# PHOTODIODE.net
KiCad netlist of a schematic drawn in Altium Designer
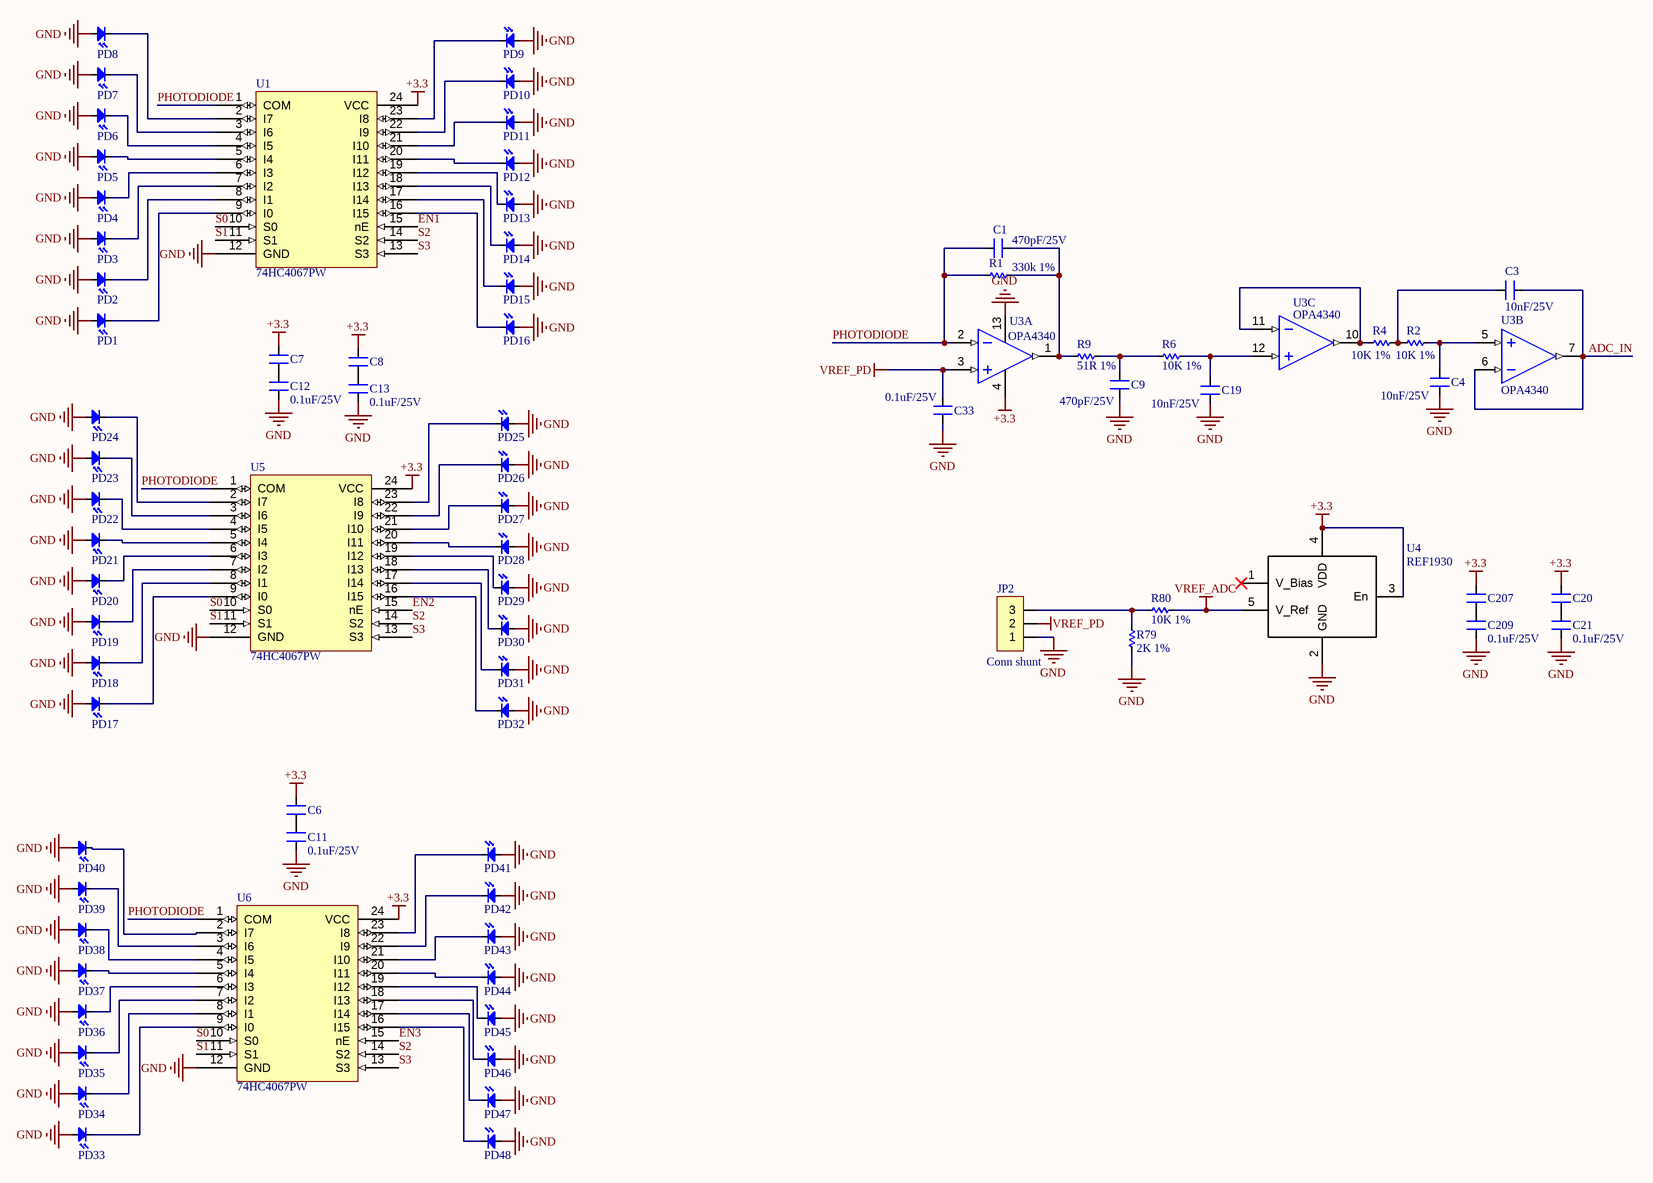
[diagram p0: PHOTODIODE.SchDoc]

(export (version "E")
  (design (tool "Eeschema 10.0.6"))
  (components
    (comp (ref "C1")
      (value "470pF/25V")
      (footprint "SM-0603")
      (description "0603")
      (libsource (lib "Capacitors") (part "CM"))
    )
    (comp (ref "C3")
      (value "10nF/25V")
      (footprint "SM-0603")
      (description "0603")
      (libsource (lib "Capacitors") (part "CM"))
    )
    (comp (ref "C4")
      (value "10nF/25V")
      (footprint "SM-0603")
      (description "0603")
      (libsource (lib "Capacitors") (part "CM"))
    )
    (comp (ref "C6")
      (value "0.1uF/25V")
      (footprint "SM-0603")
      (description "0603")
      (libsource (lib "Capacitors") (part "CM"))
    )
    (comp (ref "C7")
      (value "0.1uF/25V")
      (footprint "SM-0603")
      (description "0603")
      (libsource (lib "Capacitors") (part "CM"))
    )
    (comp (ref "C8")
      (value "0.1uF/25V")
      (footprint "SM-0603")
      (description "0603")
      (libsource (lib "Capacitors") (part "CM"))
    )
    (comp (ref "C9")
      (value "470pF/25V")
      (footprint "SM-0603")
      (description "0603")
      (libsource (lib "Capacitors") (part "CM"))
    )
    (comp (ref "C11")
      (value "0.1uF/25V")
      (footprint "SM-0603")
      (description "0603")
      (libsource (lib "Capacitors") (part "CM"))
    )
    (comp (ref "C12")
      (value "0.1uF/25V")
      (footprint "SM-0603")
      (description "0603")
      (libsource (lib "Capacitors") (part "CM"))
    )
    (comp (ref "C13")
      (value "0.1uF/25V")
      (footprint "SM-0603")
      (description "0603")
      (libsource (lib "Capacitors") (part "CM"))
    )
    (comp (ref "C19")
      (value "10nF/25V")
      (footprint "SM-0603")
      (description "0603")
      (libsource (lib "Capacitors") (part "CM"))
    )
    (comp (ref "C20")
      (value "0.1uF/25V")
      (footprint "SM-0603")
      (description "0603")
      (libsource (lib "Capacitors") (part "CM"))
    )
    (comp (ref "C21")
      (value "0.1uF/25V")
      (footprint "SM-0603")
      (description "0603")
      (libsource (lib "Capacitors") (part "CM"))
    )
    (comp (ref "C33")
      (value "0.1uF/25V")
      (footprint "SM-0603")
      (description "0603")
      (libsource (lib "Capacitors") (part "CM"))
    )
    (comp (ref "C207")
      (value "0.1uF/25V")
      (footprint "SM-0603")
      (description "0603")
      (libsource (lib "Capacitors") (part "CM"))
    )
    (comp (ref "C209")
      (value "0.1uF/25V")
      (footprint "SM-0603")
      (description "0603")
      (libsource (lib "Capacitors") (part "CM"))
    )
    (comp (ref "JP2")
      (value "Conn shunt")
      (footprint "M50-3930342")
      (description "WR-PHD 2.54 mm Angled Socket Header")
      (fields
        (field (name "MANUFACTURER") "Würth Elektronik eiSos GmbH")
        (field (name "PARTNO") "613003143121")
        (field (name "CREATED BY") "Karrer Zheng")
      )
      (libsource (lib "Library") (part "JP3"))
    )
    (comp (ref "PD1")
      (value "Photodiode")
      (footprint "VEMD5080X01")
      (libsource (lib "Library") (part "Photodiode"))
    )
    (comp (ref "PD2")
      (value "Photodiode")
      (footprint "VEMD5080X01")
      (libsource (lib "Library") (part "Photodiode"))
    )
    (comp (ref "PD3")
      (value "Photodiode")
      (footprint "VEMD5080X01")
      (libsource (lib "Library") (part "Photodiode"))
    )
    (comp (ref "PD4")
      (value "Photodiode")
      (footprint "VEMD5080X01")
      (libsource (lib "Library") (part "Photodiode"))
    )
    (comp (ref "PD5")
      (value "Photodiode")
      (footprint "VEMD5080X01")
      (libsource (lib "Library") (part "Photodiode"))
    )
    (comp (ref "PD6")
      (value "Photodiode")
      (footprint "VEMD5080X01")
      (libsource (lib "Library") (part "Photodiode"))
    )
    (comp (ref "PD7")
      (value "Photodiode")
      (footprint "VEMD5080X01")
      (libsource (lib "Library") (part "Photodiode"))
    )
    (comp (ref "PD8")
      (value "Photodiode")
      (footprint "VEMD5080X01")
      (libsource (lib "Library") (part "Photodiode"))
    )
    (comp (ref "PD9")
      (value "Photodiode")
      (footprint "VEMD5080X01")
      (libsource (lib "Library") (part "Photodiode"))
    )
    (comp (ref "PD10")
      (value "Photodiode")
      (footprint "VEMD5080X01")
      (libsource (lib "Library") (part "Photodiode"))
    )
    (comp (ref "PD11")
      (value "Photodiode")
      (footprint "VEMD5080X01")
      (libsource (lib "Library") (part "Photodiode"))
    )
    (comp (ref "PD12")
      (value "Photodiode")
      (footprint "VEMD5080X01")
      (libsource (lib "Library") (part "Photodiode"))
    )
    (comp (ref "PD13")
      (value "Photodiode")
      (footprint "VEMD5080X01")
      (libsource (lib "Library") (part "Photodiode"))
    )
    (comp (ref "PD14")
      (value "Photodiode")
      (footprint "VEMD5080X01")
      (libsource (lib "Library") (part "Photodiode"))
    )
    (comp (ref "PD15")
      (value "Photodiode")
      (footprint "VEMD5080X01")
      (libsource (lib "Library") (part "Photodiode"))
    )
    (comp (ref "PD16")
      (value "Photodiode")
      (footprint "VEMD5080X01")
      (libsource (lib "Library") (part "Photodiode"))
    )
    (comp (ref "PD17")
      (value "Photodiode")
      (footprint "VEMD5080X01")
      (libsource (lib "Library") (part "Photodiode"))
    )
    (comp (ref "PD18")
      (value "Photodiode")
      (footprint "VEMD5080X01")
      (libsource (lib "Library") (part "Photodiode"))
    )
    (comp (ref "PD19")
      (value "Photodiode")
      (footprint "VEMD5080X01")
      (libsource (lib "Library") (part "Photodiode"))
    )
    (comp (ref "PD20")
      (value "Photodiode")
      (footprint "VEMD5080X01")
      (libsource (lib "Library") (part "Photodiode"))
    )
    (comp (ref "PD21")
      (value "Photodiode")
      (footprint "VEMD5080X01")
      (libsource (lib "Library") (part "Photodiode"))
    )
    (comp (ref "PD22")
      (value "Photodiode")
      (footprint "VEMD5080X01")
      (libsource (lib "Library") (part "Photodiode"))
    )
    (comp (ref "PD23")
      (value "Photodiode")
      (footprint "VEMD5080X01")
      (libsource (lib "Library") (part "Photodiode"))
    )
    (comp (ref "PD24")
      (value "Photodiode")
      (footprint "VEMD5080X01")
      (libsource (lib "Library") (part "Photodiode"))
    )
    (comp (ref "PD25")
      (value "Photodiode")
      (footprint "VEMD5080X01")
      (libsource (lib "Library") (part "Photodiode"))
    )
    (comp (ref "PD26")
      (value "Photodiode")
      (footprint "VEMD5080X01")
      (libsource (lib "Library") (part "Photodiode"))
    )
    (comp (ref "PD27")
      (value "Photodiode")
      (footprint "VEMD5080X01")
      (libsource (lib "Library") (part "Photodiode"))
    )
    (comp (ref "PD28")
      (value "Photodiode")
      (footprint "VEMD5080X01")
      (libsource (lib "Library") (part "Photodiode"))
    )
    (comp (ref "PD29")
      (value "Photodiode")
      (footprint "VEMD5080X01")
      (libsource (lib "Library") (part "Photodiode"))
    )
    (comp (ref "PD30")
      (value "Photodiode")
      (footprint "VEMD5080X01")
      (libsource (lib "Library") (part "Photodiode"))
    )
    (comp (ref "PD31")
      (value "Photodiode")
      (footprint "VEMD5080X01")
      (libsource (lib "Library") (part "Photodiode"))
    )
    (comp (ref "PD32")
      (value "Photodiode")
      (footprint "VEMD5080X01")
      (libsource (lib "Library") (part "Photodiode"))
    )
    (comp (ref "PD33")
      (value "Photodiode")
      (footprint "VEMD5080X01")
      (libsource (lib "Library") (part "Photodiode"))
    )
    (comp (ref "PD34")
      (value "Photodiode")
      (footprint "VEMD5080X01")
      (libsource (lib "Library") (part "Photodiode"))
    )
    (comp (ref "PD35")
      (value "Photodiode")
      (footprint "VEMD5080X01")
      (libsource (lib "Library") (part "Photodiode"))
    )
    (comp (ref "PD36")
      (value "Photodiode")
      (footprint "VEMD5080X01")
      (libsource (lib "Library") (part "Photodiode"))
    )
    (comp (ref "PD37")
      (value "Photodiode")
      (footprint "VEMD5080X01")
      (libsource (lib "Library") (part "Photodiode"))
    )
    (comp (ref "PD38")
      (value "Photodiode")
      (footprint "VEMD5080X01")
      (libsource (lib "Library") (part "Photodiode"))
    )
    (comp (ref "PD39")
      (value "Photodiode")
      (footprint "VEMD5080X01")
      (libsource (lib "Library") (part "Photodiode"))
    )
    (comp (ref "PD40")
      (value "Photodiode")
      (footprint "VEMD5080X01")
      (libsource (lib "Library") (part "Photodiode"))
    )
    (comp (ref "PD41")
      (value "Photodiode")
      (footprint "VEMD5080X01")
      (libsource (lib "Library") (part "Photodiode"))
    )
    (comp (ref "PD42")
      (value "Photodiode")
      (footprint "VEMD5080X01")
      (libsource (lib "Library") (part "Photodiode"))
    )
    (comp (ref "PD43")
      (value "Photodiode")
      (footprint "VEMD5080X01")
      (libsource (lib "Library") (part "Photodiode"))
    )
    (comp (ref "PD44")
      (value "Photodiode")
      (footprint "VEMD5080X01")
      (libsource (lib "Library") (part "Photodiode"))
    )
    (comp (ref "PD45")
      (value "Photodiode")
      (footprint "VEMD5080X01")
      (libsource (lib "Library") (part "Photodiode"))
    )
    (comp (ref "PD46")
      (value "Photodiode")
      (footprint "VEMD5080X01")
      (libsource (lib "Library") (part "Photodiode"))
    )
    (comp (ref "PD47")
      (value "Photodiode")
      (footprint "VEMD5080X01")
      (libsource (lib "Library") (part "Photodiode"))
    )
    (comp (ref "PD48")
      (value "Photodiode")
      (footprint "VEMD5080X01")
      (libsource (lib "Library") (part "Photodiode"))
    )
    (comp (ref "R1")
      (value "330k 1%")
      (footprint "RES-SMD-0603")
      (description "0603")
      (fields
        (field (name "MANUFACTURER") "Generic Components")
        (field (name "PUBLISHER") "Altium Hobart Technology Centre")
      )
      (libsource (lib "Library") (part "Res-SMD"))
    )
    (comp (ref "R2")
      (value "10K 1%")
      (footprint "RES-SMD-0603")
      (description "0603")
      (fields
        (field (name "MANUFACTURER") "Generic Components")
        (field (name "PUBLISHER") "Altium Hobart Technology Centre")
      )
      (libsource (lib "Library") (part "Res-SMD"))
    )
    (comp (ref "R4")
      (value "10K 1%")
      (footprint "RES-SMD-0603")
      (description "0603")
      (fields
        (field (name "MANUFACTURER") "Generic Components")
        (field (name "PUBLISHER") "Altium Hobart Technology Centre")
      )
      (libsource (lib "Library") (part "Res-SMD"))
    )
    (comp (ref "R6")
      (value "10K 1%")
      (footprint "RES-SMD-0603")
      (description "0603")
      (fields
        (field (name "MANUFACTURER") "Generic Components")
        (field (name "PUBLISHER") "Altium Hobart Technology Centre")
      )
      (libsource (lib "Library") (part "Res-SMD"))
    )
    (comp (ref "R9")
      (value "51R 1%")
      (footprint "RES-SMD-0603")
      (description "0603")
      (fields
        (field (name "MANUFACTURER") "Generic Components")
        (field (name "PUBLISHER") "Altium Hobart Technology Centre")
      )
      (libsource (lib "Library") (part "Res-SMD"))
    )
    (comp (ref "R79")
      (value "2K 1%")
      (footprint "RES-SMD-0603")
      (description "0603")
      (fields
        (field (name "MANUFACTURER") "Generic Components")
        (field (name "PUBLISHER") "Altium Hobart Technology Centre")
      )
      (libsource (lib "Library") (part "Res-SMD"))
    )
    (comp (ref "R80")
      (value "10K 1%")
      (footprint "RES-SMD-0603")
      (description "0603")
      (fields
        (field (name "MANUFACTURER") "Generic Components")
        (field (name "PUBLISHER") "Altium Hobart Technology Centre")
      )
      (libsource (lib "Library") (part "Res-SMD"))
    )
    (comp (ref "U1")
      (value "74HC4067PW")
      (footprint "TSSOP24")
      (description "TSSOP24")
      (libsource (lib "Library") (part "74HC4067PW"))
    )
    (comp (ref "U3")
      (value "OPA4340")
      (footprint "SSOP16")
      (description "IC CMOS 4 CIRCUIT 16SSOP")
      (libsource (lib "Library") (part "OPA4340"))
    )
    (comp (ref "U4")
      (value "REF1930")
      (footprint "SOT23-5")
      (description "REF1941AIDDCT")
      (libsource (lib "Library") (part "REF19xx"))
    )
    (comp (ref "U5")
      (value "74HC4067PW")
      (footprint "TSSOP24")
      (description "TSSOP24")
      (libsource (lib "Library") (part "74HC4067PW"))
    )
    (comp (ref "U6")
      (value "74HC4067PW")
      (footprint "TSSOP24")
      (description "TSSOP24")
      (libsource (lib "Library") (part "74HC4067PW"))
    )
  )
  (nets
    (net (code "1") (name "+3.3") (class "Default")
      (node (ref "C20") (pin "2") (pinfunction "2_2") (pintype "passive"))
      (node (ref "C207") (pin "2") (pinfunction "2_2") (pintype "passive"))
      (node (ref "C6") (pin "2") (pinfunction "2_2") (pintype "passive"))
      (node (ref "C7") (pin "2") (pinfunction "2_2") (pintype "passive"))
      (node (ref "C8") (pin "2") (pinfunction "2_2") (pintype "passive"))
      (node (ref "U1") (pin "24") (pinfunction "VCC_24") (pintype "power_in"))
      (node (ref "U3") (pin "4") (pinfunction "+V_4") (pintype "passive"))
      (node (ref "U4") (pin "3") (pinfunction "En_3") (pintype "passive"))
      (node (ref "U4") (pin "4") (pinfunction "VDD_4") (pintype "passive"))
      (node (ref "U5") (pin "24") (pinfunction "VCC_24") (pintype "power_in"))
      (node (ref "U6") (pin "24") (pinfunction "VCC_24") (pintype "power_in"))
    )
    (net (code "2") (name "/ADC_IN") (class "Default")
      (node (ref "C3") (pin "1") (pinfunction "1_1") (pintype "passive"))
      (node (ref "U3") (pin "6") (pinfunction "IN-_6") (pintype "input"))
      (node (ref "U3") (pin "7") (pinfunction "OUT_7") (pintype "output"))
    )
    (net (code "3") (name "/EN1") (class "Default")
      (node (ref "U1") (pin "15") (pinfunction "nE_15") (pintype "input"))
    )
    (net (code "4") (name "/EN2") (class "Default")
      (node (ref "U5") (pin "15") (pinfunction "nE_15") (pintype "input"))
    )
    (net (code "5") (name "/EN3") (class "Default")
      (node (ref "U6") (pin "15") (pinfunction "nE_15") (pintype "input"))
    )
    (net (code "6") (name "/PHOTODIODE") (class "Default")
      (node (ref "C1") (pin "1") (pinfunction "1_1") (pintype "passive"))
      (node (ref "R1") (pin "1") (pinfunction "1_1") (pintype "passive"))
      (node (ref "U1") (pin "1") (pinfunction "COM_1") (pintype "bidirectional"))
      (node (ref "U3") (pin "2") (pinfunction "IN-_2") (pintype "input"))
      (node (ref "U5") (pin "1") (pinfunction "COM_1") (pintype "bidirectional"))
      (node (ref "U6") (pin "1") (pinfunction "COM_1") (pintype "bidirectional"))
    )
    (net (code "7") (name "/S0") (class "Default")
      (node (ref "U1") (pin "10") (pinfunction "S0_10") (pintype "input"))
      (node (ref "U5") (pin "10") (pinfunction "S0_10") (pintype "input"))
      (node (ref "U6") (pin "10") (pinfunction "S0_10") (pintype "input"))
    )
    (net (code "8") (name "/S1") (class "Default")
      (node (ref "U1") (pin "11") (pinfunction "S1_11") (pintype "input"))
      (node (ref "U5") (pin "11") (pinfunction "S1_11") (pintype "input"))
      (node (ref "U6") (pin "11") (pinfunction "S1_11") (pintype "input"))
    )
    (net (code "9") (name "/S2") (class "Default")
      (node (ref "U1") (pin "14") (pinfunction "S2_14") (pintype "input"))
      (node (ref "U5") (pin "14") (pinfunction "S2_14") (pintype "input"))
      (node (ref "U6") (pin "14") (pinfunction "S2_14") (pintype "input"))
    )
    (net (code "10") (name "/S3") (class "Default")
      (node (ref "U1") (pin "13") (pinfunction "S3_13") (pintype "input"))
      (node (ref "U5") (pin "13") (pinfunction "S3_13") (pintype "input"))
      (node (ref "U6") (pin "13") (pinfunction "S3_13") (pintype "input"))
    )
    (net (code "11") (name "GND") (class "Default")
      (node (ref "C11") (pin "1") (pinfunction "1_1") (pintype "passive"))
      (node (ref "C12") (pin "1") (pinfunction "1_1") (pintype "passive"))
      (node (ref "C13") (pin "1") (pinfunction "1_1") (pintype "passive"))
      (node (ref "C19") (pin "1") (pinfunction "1_1") (pintype "passive"))
      (node (ref "C209") (pin "1") (pinfunction "1_1") (pintype "passive"))
      (node (ref "C21") (pin "1") (pinfunction "1_1") (pintype "passive"))
      (node (ref "C33") (pin "1") (pinfunction "1_1") (pintype "passive"))
      (node (ref "C4") (pin "1") (pinfunction "1_1") (pintype "passive"))
      (node (ref "C9") (pin "1") (pinfunction "1_1") (pintype "passive"))
      (node (ref "JP2") (pin "1") (pinfunction "1_1") (pintype "passive"))
      (node (ref "PD1") (pin "1") (pinfunction "A_1") (pintype "passive"))
      (node (ref "PD10") (pin "1") (pinfunction "A_1") (pintype "passive"))
      (node (ref "PD11") (pin "1") (pinfunction "A_1") (pintype "passive"))
      (node (ref "PD12") (pin "1") (pinfunction "A_1") (pintype "passive"))
      (node (ref "PD13") (pin "1") (pinfunction "A_1") (pintype "passive"))
      (node (ref "PD14") (pin "1") (pinfunction "A_1") (pintype "passive"))
      (node (ref "PD15") (pin "1") (pinfunction "A_1") (pintype "passive"))
      (node (ref "PD16") (pin "1") (pinfunction "A_1") (pintype "passive"))
      (node (ref "PD17") (pin "1") (pinfunction "A_1") (pintype "passive"))
      (node (ref "PD18") (pin "1") (pinfunction "A_1") (pintype "passive"))
      (node (ref "PD19") (pin "1") (pinfunction "A_1") (pintype "passive"))
      (node (ref "PD2") (pin "1") (pinfunction "A_1") (pintype "passive"))
      (node (ref "PD20") (pin "1") (pinfunction "A_1") (pintype "passive"))
      (node (ref "PD21") (pin "1") (pinfunction "A_1") (pintype "passive"))
      (node (ref "PD22") (pin "1") (pinfunction "A_1") (pintype "passive"))
      (node (ref "PD23") (pin "1") (pinfunction "A_1") (pintype "passive"))
      (node (ref "PD24") (pin "1") (pinfunction "A_1") (pintype "passive"))
      (node (ref "PD25") (pin "1") (pinfunction "A_1") (pintype "passive"))
      (node (ref "PD26") (pin "1") (pinfunction "A_1") (pintype "passive"))
      (node (ref "PD27") (pin "1") (pinfunction "A_1") (pintype "passive"))
      (node (ref "PD28") (pin "1") (pinfunction "A_1") (pintype "passive"))
      (node (ref "PD29") (pin "1") (pinfunction "A_1") (pintype "passive"))
      (node (ref "PD3") (pin "1") (pinfunction "A_1") (pintype "passive"))
      (node (ref "PD30") (pin "1") (pinfunction "A_1") (pintype "passive"))
      (node (ref "PD31") (pin "1") (pinfunction "A_1") (pintype "passive"))
      (node (ref "PD32") (pin "1") (pinfunction "A_1") (pintype "passive"))
      (node (ref "PD33") (pin "1") (pinfunction "A_1") (pintype "passive"))
      (node (ref "PD34") (pin "1") (pinfunction "A_1") (pintype "passive"))
      (node (ref "PD35") (pin "1") (pinfunction "A_1") (pintype "passive"))
      (node (ref "PD36") (pin "1") (pinfunction "A_1") (pintype "passive"))
      (node (ref "PD37") (pin "1") (pinfunction "A_1") (pintype "passive"))
      (node (ref "PD38") (pin "1") (pinfunction "A_1") (pintype "passive"))
      (node (ref "PD39") (pin "1") (pinfunction "A_1") (pintype "passive"))
      (node (ref "PD4") (pin "1") (pinfunction "A_1") (pintype "passive"))
      (node (ref "PD40") (pin "1") (pinfunction "A_1") (pintype "passive"))
      (node (ref "PD41") (pin "1") (pinfunction "A_1") (pintype "passive"))
      (node (ref "PD42") (pin "1") (pinfunction "A_1") (pintype "passive"))
      (node (ref "PD43") (pin "1") (pinfunction "A_1") (pintype "passive"))
      (node (ref "PD44") (pin "1") (pinfunction "A_1") (pintype "passive"))
      (node (ref "PD45") (pin "1") (pinfunction "A_1") (pintype "passive"))
      (node (ref "PD46") (pin "1") (pinfunction "A_1") (pintype "passive"))
      (node (ref "PD47") (pin "1") (pinfunction "A_1") (pintype "passive"))
      (node (ref "PD48") (pin "1") (pinfunction "A_1") (pintype "passive"))
      (node (ref "PD5") (pin "1") (pinfunction "A_1") (pintype "passive"))
      (node (ref "PD6") (pin "1") (pinfunction "A_1") (pintype "passive"))
      (node (ref "PD7") (pin "1") (pinfunction "A_1") (pintype "passive"))
      (node (ref "PD8") (pin "1") (pinfunction "A_1") (pintype "passive"))
      (node (ref "PD9") (pin "1") (pinfunction "A_1") (pintype "passive"))
      (node (ref "R79") (pin "1") (pinfunction "1_1") (pintype "passive"))
      (node (ref "U1") (pin "12") (pinfunction "GND_12") (pintype "power_in"))
      (node (ref "U3") (pin "13") (pinfunction "-V_13") (pintype "passive"))
      (node (ref "U4") (pin "2") (pinfunction "GND_2") (pintype "passive"))
      (node (ref "U5") (pin "12") (pinfunction "GND_12") (pintype "power_in"))
      (node (ref "U6") (pin "12") (pinfunction "GND_12") (pintype "power_in"))
    )
    (net (code "12") (name "Net-(C3-Pad2)") (class "Default")
      (node (ref "C3") (pin "2") (pinfunction "2_2") (pintype "passive"))
      (node (ref "R2") (pin "1") (pinfunction "1_1") (pintype "passive"))
      (node (ref "R4") (pin "2") (pinfunction "2_2") (pintype "passive"))
    )
    (net (code "13") (name "Net-(C9-Pad2)") (class "Default")
      (node (ref "C9") (pin "2") (pinfunction "2_2") (pintype "passive"))
      (node (ref "R6") (pin "1") (pinfunction "1_1") (pintype "passive"))
      (node (ref "R9") (pin "2") (pinfunction "2_2") (pintype "passive"))
    )
    (net (code "14") (name "Net-(C11-Pad2)") (class "Default")
      (node (ref "C11") (pin "2") (pinfunction "2_2") (pintype "passive"))
      (node (ref "C6") (pin "1") (pinfunction "1_1") (pintype "passive"))
    )
    (net (code "15") (name "Net-(C12-Pad2)") (class "Default")
      (node (ref "C12") (pin "2") (pinfunction "2_2") (pintype "passive"))
      (node (ref "C7") (pin "1") (pinfunction "1_1") (pintype "passive"))
    )
    (net (code "16") (name "Net-(C13-Pad2)") (class "Default")
      (node (ref "C13") (pin "2") (pinfunction "2_2") (pintype "passive"))
      (node (ref "C8") (pin "1") (pinfunction "1_1") (pintype "passive"))
    )
    (net (code "17") (name "Net-(C20-Pad1)") (class "Default")
      (node (ref "C20") (pin "1") (pinfunction "1_1") (pintype "passive"))
      (node (ref "C21") (pin "2") (pinfunction "2_2") (pintype "passive"))
    )
    (net (code "18") (name "Net-(C207-Pad1)") (class "Default")
      (node (ref "C207") (pin "1") (pinfunction "1_1") (pintype "passive"))
      (node (ref "C209") (pin "2") (pinfunction "2_2") (pintype "passive"))
    )
    (net (code "19") (name "Net-(JP2-Pad3)") (class "Default")
      (node (ref "JP2") (pin "3") (pinfunction "3_3") (pintype "passive"))
      (node (ref "R79") (pin "2") (pinfunction "2_2") (pintype "passive"))
      (node (ref "R80") (pin "2") (pinfunction "2_2") (pintype "passive"))
    )
    (net (code "20") (name "Net-(PD1-K)") (class "Default")
      (node (ref "PD1") (pin "2") (pinfunction "K_2") (pintype "passive"))
      (node (ref "U1") (pin "9") (pinfunction "I0_9") (pintype "bidirectional"))
    )
    (net (code "21") (name "Net-(PD2-K)") (class "Default")
      (node (ref "PD2") (pin "2") (pinfunction "K_2") (pintype "passive"))
      (node (ref "U1") (pin "8") (pinfunction "I1_8") (pintype "bidirectional"))
    )
    (net (code "22") (name "Net-(PD3-K)") (class "Default")
      (node (ref "PD3") (pin "2") (pinfunction "K_2") (pintype "passive"))
      (node (ref "U1") (pin "7") (pinfunction "I2_7") (pintype "bidirectional"))
    )
    (net (code "23") (name "Net-(PD4-K)") (class "Default")
      (node (ref "PD4") (pin "2") (pinfunction "K_2") (pintype "passive"))
      (node (ref "U1") (pin "6") (pinfunction "I3_6") (pintype "bidirectional"))
    )
    (net (code "24") (name "Net-(PD5-K)") (class "Default")
      (node (ref "PD5") (pin "2") (pinfunction "K_2") (pintype "passive"))
      (node (ref "U1") (pin "5") (pinfunction "I4_5") (pintype "bidirectional"))
    )
    (net (code "25") (name "Net-(PD6-K)") (class "Default")
      (node (ref "PD6") (pin "2") (pinfunction "K_2") (pintype "passive"))
      (node (ref "U1") (pin "4") (pinfunction "I5_4") (pintype "bidirectional"))
    )
    (net (code "26") (name "Net-(PD7-K)") (class "Default")
      (node (ref "PD7") (pin "2") (pinfunction "K_2") (pintype "passive"))
      (node (ref "U1") (pin "3") (pinfunction "I6_3") (pintype "bidirectional"))
    )
    (net (code "27") (name "Net-(PD8-K)") (class "Default")
      (node (ref "PD8") (pin "2") (pinfunction "K_2") (pintype "passive"))
      (node (ref "U1") (pin "2") (pinfunction "I7_2") (pintype "bidirectional"))
    )
    (net (code "28") (name "Net-(PD9-K)") (class "Default")
      (node (ref "PD9") (pin "2") (pinfunction "K_2") (pintype "passive"))
      (node (ref "U1") (pin "23") (pinfunction "I8_23") (pintype "bidirectional"))
    )
    (net (code "29") (name "Net-(PD10-K)") (class "Default")
      (node (ref "PD10") (pin "2") (pinfunction "K_2") (pintype "passive"))
      (node (ref "U1") (pin "22") (pinfunction "I9_22") (pintype "bidirectional"))
    )
    (net (code "30") (name "Net-(PD11-K)") (class "Default")
      (node (ref "PD11") (pin "2") (pinfunction "K_2") (pintype "passive"))
      (node (ref "U1") (pin "21") (pinfunction "I10_21") (pintype "bidirectional"))
    )
    (net (code "31") (name "Net-(PD12-K)") (class "Default")
      (node (ref "PD12") (pin "2") (pinfunction "K_2") (pintype "passive"))
      (node (ref "U1") (pin "20") (pinfunction "I11_20") (pintype "bidirectional"))
    )
    (net (code "32") (name "Net-(PD13-K)") (class "Default")
      (node (ref "PD13") (pin "2") (pinfunction "K_2") (pintype "passive"))
      (node (ref "U1") (pin "19") (pinfunction "I12_19") (pintype "bidirectional"))
    )
    (net (code "33") (name "Net-(PD14-K)") (class "Default")
      (node (ref "PD14") (pin "2") (pinfunction "K_2") (pintype "passive"))
      (node (ref "U1") (pin "18") (pinfunction "I13_18") (pintype "bidirectional"))
    )
    (net (code "34") (name "Net-(PD15-K)") (class "Default")
      (node (ref "PD15") (pin "2") (pinfunction "K_2") (pintype "passive"))
      (node (ref "U1") (pin "17") (pinfunction "I14_17") (pintype "bidirectional"))
    )
    (net (code "35") (name "Net-(PD16-K)") (class "Default")
      (node (ref "PD16") (pin "2") (pinfunction "K_2") (pintype "passive"))
      (node (ref "U1") (pin "16") (pinfunction "I15_16") (pintype "bidirectional"))
    )
    (net (code "36") (name "Net-(PD17-K)") (class "Default")
      (node (ref "PD17") (pin "2") (pinfunction "K_2") (pintype "passive"))
      (node (ref "U5") (pin "9") (pinfunction "I0_9") (pintype "bidirectional"))
    )
    (net (code "37") (name "Net-(PD18-K)") (class "Default")
      (node (ref "PD18") (pin "2") (pinfunction "K_2") (pintype "passive"))
      (node (ref "U5") (pin "8") (pinfunction "I1_8") (pintype "bidirectional"))
    )
    (net (code "38") (name "Net-(PD19-K)") (class "Default")
      (node (ref "PD19") (pin "2") (pinfunction "K_2") (pintype "passive"))
      (node (ref "U5") (pin "7") (pinfunction "I2_7") (pintype "bidirectional"))
    )
    (net (code "39") (name "Net-(PD20-K)") (class "Default")
      (node (ref "PD20") (pin "2") (pinfunction "K_2") (pintype "passive"))
      (node (ref "U5") (pin "6") (pinfunction "I3_6") (pintype "bidirectional"))
    )
    (net (code "40") (name "Net-(PD21-K)") (class "Default")
      (node (ref "PD21") (pin "2") (pinfunction "K_2") (pintype "passive"))
      (node (ref "U5") (pin "5") (pinfunction "I4_5") (pintype "bidirectional"))
    )
    (net (code "41") (name "Net-(PD22-K)") (class "Default")
      (node (ref "PD22") (pin "2") (pinfunction "K_2") (pintype "passive"))
      (node (ref "U5") (pin "4") (pinfunction "I5_4") (pintype "bidirectional"))
    )
    (net (code "42") (name "Net-(PD23-K)") (class "Default")
      (node (ref "PD23") (pin "2") (pinfunction "K_2") (pintype "passive"))
      (node (ref "U5") (pin "3") (pinfunction "I6_3") (pintype "bidirectional"))
    )
    (net (code "43") (name "Net-(PD24-K)") (class "Default")
      (node (ref "PD24") (pin "2") (pinfunction "K_2") (pintype "passive"))
      (node (ref "U5") (pin "2") (pinfunction "I7_2") (pintype "bidirectional"))
    )
    (net (code "44") (name "Net-(PD25-K)") (class "Default")
      (node (ref "PD25") (pin "2") (pinfunction "K_2") (pintype "passive"))
      (node (ref "U5") (pin "23") (pinfunction "I8_23") (pintype "bidirectional"))
    )
    (net (code "45") (name "Net-(PD26-K)") (class "Default")
      (node (ref "PD26") (pin "2") (pinfunction "K_2") (pintype "passive"))
      (node (ref "U5") (pin "22") (pinfunction "I9_22") (pintype "bidirectional"))
    )
    (net (code "46") (name "Net-(PD27-K)") (class "Default")
      (node (ref "PD27") (pin "2") (pinfunction "K_2") (pintype "passive"))
      (node (ref "U5") (pin "21") (pinfunction "I10_21") (pintype "bidirectional"))
    )
    (net (code "47") (name "Net-(PD28-K)") (class "Default")
      (node (ref "PD28") (pin "2") (pinfunction "K_2") (pintype "passive"))
      (node (ref "U5") (pin "20") (pinfunction "I11_20") (pintype "bidirectional"))
    )
    (net (code "48") (name "Net-(PD29-K)") (class "Default")
      (node (ref "PD29") (pin "2") (pinfunction "K_2") (pintype "passive"))
      (node (ref "U5") (pin "19") (pinfunction "I12_19") (pintype "bidirectional"))
    )
    (net (code "49") (name "Net-(PD30-K)") (class "Default")
      (node (ref "PD30") (pin "2") (pinfunction "K_2") (pintype "passive"))
      (node (ref "U5") (pin "18") (pinfunction "I13_18") (pintype "bidirectional"))
    )
    (net (code "50") (name "Net-(PD31-K)") (class "Default")
      (node (ref "PD31") (pin "2") (pinfunction "K_2") (pintype "passive"))
      (node (ref "U5") (pin "17") (pinfunction "I14_17") (pintype "bidirectional"))
    )
    (net (code "51") (name "Net-(PD32-K)") (class "Default")
      (node (ref "PD32") (pin "2") (pinfunction "K_2") (pintype "passive"))
      (node (ref "U5") (pin "16") (pinfunction "I15_16") (pintype "bidirectional"))
    )
    (net (code "52") (name "Net-(PD33-K)") (class "Default")
      (node (ref "PD33") (pin "2") (pinfunction "K_2") (pintype "passive"))
      (node (ref "U6") (pin "9") (pinfunction "I0_9") (pintype "bidirectional"))
    )
    (net (code "53") (name "Net-(PD34-K)") (class "Default")
      (node (ref "PD34") (pin "2") (pinfunction "K_2") (pintype "passive"))
      (node (ref "U6") (pin "8") (pinfunction "I1_8") (pintype "bidirectional"))
    )
    (net (code "54") (name "Net-(PD35-K)") (class "Default")
      (node (ref "PD35") (pin "2") (pinfunction "K_2") (pintype "passive"))
      (node (ref "U6") (pin "7") (pinfunction "I2_7") (pintype "bidirectional"))
    )
    (net (code "55") (name "Net-(PD36-K)") (class "Default")
      (node (ref "PD36") (pin "2") (pinfunction "K_2") (pintype "passive"))
      (node (ref "U6") (pin "6") (pinfunction "I3_6") (pintype "bidirectional"))
    )
    (net (code "56") (name "Net-(PD37-K)") (class "Default")
      (node (ref "PD37") (pin "2") (pinfunction "K_2") (pintype "passive"))
      (node (ref "U6") (pin "5") (pinfunction "I4_5") (pintype "bidirectional"))
    )
    (net (code "57") (name "Net-(PD38-K)") (class "Default")
      (node (ref "PD38") (pin "2") (pinfunction "K_2") (pintype "passive"))
      (node (ref "U6") (pin "4") (pinfunction "I5_4") (pintype "bidirectional"))
    )
    (net (code "58") (name "Net-(PD39-K)") (class "Default")
      (node (ref "PD39") (pin "2") (pinfunction "K_2") (pintype "passive"))
      (node (ref "U6") (pin "3") (pinfunction "I6_3") (pintype "bidirectional"))
    )
    (net (code "59") (name "Net-(PD40-K)") (class "Default")
      (node (ref "PD40") (pin "2") (pinfunction "K_2") (pintype "passive"))
      (node (ref "U6") (pin "2") (pinfunction "I7_2") (pintype "bidirectional"))
    )
    (net (code "60") (name "Net-(PD41-K)") (class "Default")
      (node (ref "PD41") (pin "2") (pinfunction "K_2") (pintype "passive"))
      (node (ref "U6") (pin "23") (pinfunction "I8_23") (pintype "bidirectional"))
    )
    (net (code "61") (name "Net-(PD42-K)") (class "Default")
      (node (ref "PD42") (pin "2") (pinfunction "K_2") (pintype "passive"))
      (node (ref "U6") (pin "22") (pinfunction "I9_22") (pintype "bidirectional"))
    )
    (net (code "62") (name "Net-(PD43-K)") (class "Default")
      (node (ref "PD43") (pin "2") (pinfunction "K_2") (pintype "passive"))
      (node (ref "U6") (pin "21") (pinfunction "I10_21") (pintype "bidirectional"))
    )
    (net (code "63") (name "Net-(PD44-K)") (class "Default")
      (node (ref "PD44") (pin "2") (pinfunction "K_2") (pintype "passive"))
      (node (ref "U6") (pin "20") (pinfunction "I11_20") (pintype "bidirectional"))
    )
    (net (code "64") (name "Net-(PD45-K)") (class "Default")
      (node (ref "PD45") (pin "2") (pinfunction "K_2") (pintype "passive"))
      (node (ref "U6") (pin "19") (pinfunction "I12_19") (pintype "bidirectional"))
    )
    (net (code "65") (name "Net-(PD46-K)") (class "Default")
      (node (ref "PD46") (pin "2") (pinfunction "K_2") (pintype "passive"))
      (node (ref "U6") (pin "18") (pinfunction "I13_18") (pintype "bidirectional"))
    )
    (net (code "66") (name "Net-(PD47-K)") (class "Default")
      (node (ref "PD47") (pin "2") (pinfunction "K_2") (pintype "passive"))
      (node (ref "U6") (pin "17") (pinfunction "I14_17") (pintype "bidirectional"))
    )
    (net (code "67") (name "Net-(PD48-K)") (class "Default")
      (node (ref "PD48") (pin "2") (pinfunction "K_2") (pintype "passive"))
      (node (ref "U6") (pin "16") (pinfunction "I15_16") (pintype "bidirectional"))
    )
    (net (code "68") (name "Net-(U3A-OUT)") (class "Default")
      (node (ref "C1") (pin "2") (pinfunction "2_2") (pintype "passive"))
      (node (ref "R1") (pin "2") (pinfunction "2_2") (pintype "passive"))
      (node (ref "R9") (pin "1") (pinfunction "1_1") (pintype "passive"))
      (node (ref "U3") (pin "1") (pinfunction "OUT_1") (pintype "output"))
    )
    (net (code "69") (name "Net-(U3B-IN+)") (class "Default")
      (node (ref "C4") (pin "2") (pinfunction "2_2") (pintype "passive"))
      (node (ref "R2") (pin "2") (pinfunction "2_2") (pintype "passive"))
      (node (ref "U3") (pin "5") (pinfunction "IN+_5") (pintype "input"))
    )
    (net (code "70") (name "Net-(U3C-IN+)") (class "Default")
      (node (ref "C19") (pin "2") (pinfunction "2_2") (pintype "passive"))
      (node (ref "R6") (pin "2") (pinfunction "2_2") (pintype "passive"))
      (node (ref "U3") (pin "12") (pinfunction "IN+_12") (pintype "input"))
    )
    (net (code "71") (name "Net-(U3C-IN-)") (class "Default")
      (node (ref "R4") (pin "1") (pinfunction "1_1") (pintype "passive"))
      (node (ref "U3") (pin "10") (pinfunction "OUT_10") (pintype "output"))
      (node (ref "U3") (pin "11") (pinfunction "IN-_11") (pintype "input"))
    )
    (net (code "72") (name "VREF_ADC") (class "Default")
      (node (ref "R80") (pin "1") (pinfunction "1_1") (pintype "passive"))
      (node (ref "U4") (pin "5") (pinfunction "V_Ref_5") (pintype "passive"))
    )
    (net (code "73") (name "VREF_PD") (class "Default")
      (node (ref "C33") (pin "2") (pinfunction "2_2") (pintype "passive"))
      (node (ref "JP2") (pin "2") (pinfunction "2_2") (pintype "passive"))
      (node (ref "U3") (pin "3") (pinfunction "IN+_3") (pintype "input"))
    )
    (net (code "74") (name "unconnected-(U4-V_Bias-Pad1)") (class "Default")
      (node (ref "U4") (pin "1") (pinfunction "V_Bias_1") (pintype "passive+no_connect"))
    )
  )
)
